# Power_Distribution_-_Spares_8-9_5V.net
KiCad netlist of a schematic drawn in Altium Designer
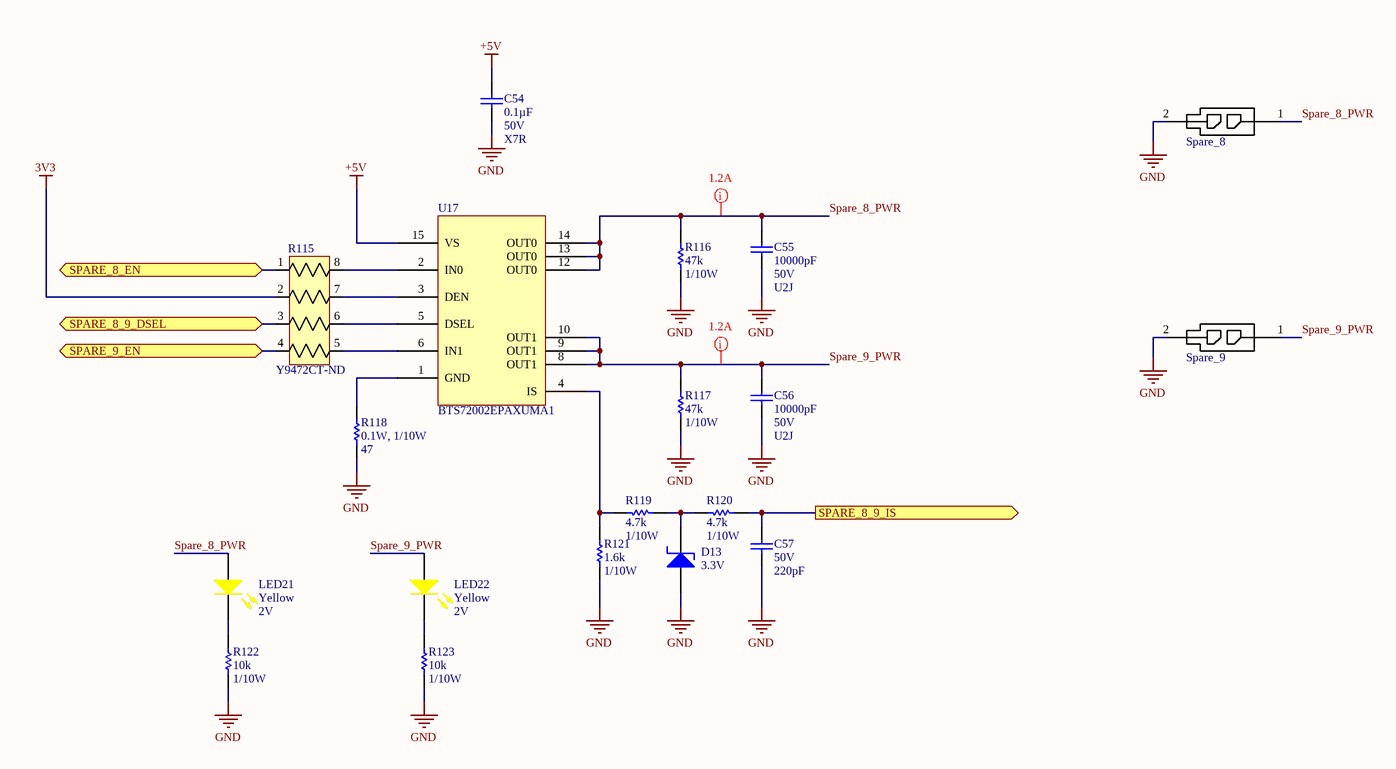
[diagram p0: Power Distribution - Spares 8-9 (5V).SchDoc]

(export (version "E")
  (design (tool "Eeschema 10.0.6"))
  (components
    (comp (ref "C54")
      (value "CAP CER 0.1UF 50V 10% X7R 0603")
      (footprint "CAP, 0603")
      (description "0.10µF ±10% 50V Ceramic Capacitor X7R 0603 (1608 Metric)")
      (fields
        (field (name "TOLERANCE") "±10%")
        (field (name "CAPACITANCE") "0.1µF")
        (field (name "VOLTAGE") "50V")
        (field (name "TEMPERATURE COEFFICIENT") "X7R")
      )
      (libsource (lib "Schematic Diagrams") (part "CAP CER 0.1UF 50V 10% X7R 0603"))
    )
    (comp (ref "C55")
      (value "CAP CER 10nF 50V 5% X7R 0603")
      (footprint "CAP, 0603")
      (description "10000pF ±5% 50V Ceramic Capacitor U2J 0603 (1608 Metric)")
      (fields
        (field (name "TOLERANCE") "±5%")
        (field (name "CAPACITANCE") "10000pF")
        (field (name "VOLTAGE") "50V")
        (field (name "TEMPERATURE COEFFICIENT") "U2J")
      )
      (libsource (lib "Schematic Diagrams") (part "CAP CER 10nF 50V 5% X7R 0603"))
    )
    (comp (ref "C56")
      (value "CAP CER 10nF 50V 5% X7R 0603")
      (footprint "CAP, 0603")
      (description "10000pF ±5% 50V Ceramic Capacitor U2J 0603 (1608 Metric)")
      (fields
        (field (name "TOLERANCE") "±5%")
        (field (name "CAPACITANCE") "10000pF")
        (field (name "VOLTAGE") "50V")
        (field (name "TEMPERATURE COEFFICIENT") "U2J")
      )
      (libsource (lib "Schematic Diagrams") (part "CAP CER 10nF 50V 5% X7R 0603"))
    )
    (comp (ref "C57")
      (value "CAP CER 220PF 50V C0G/NP0 0603")
      (footprint "CAP, 0603")
      (description "220pF ±5% 50V Ceramic Capacitor C0G, NP0 0603 (1608 Metric)")
      (fields
        (field (name "MANUFACTURER") "KEMET")
        (field (name "TOLERANCE") "5%")
        (field (name "VOLTAGE RATING") "50V")
        (field (name "CAPACITANCE") "220pF")
      )
      (libsource (lib "Schematic Diagrams") (part "CAP CER 220PF 50V C0G/NP0 0603"))
    )
    (comp (ref "D13")
      (value "DIODE ZENER 3.3V 200MW SOD323")
      (footprint "sod-323")
      (description "Zener Diode 3.3V 200mW ±5% Surface Mount SOD-323")
      (fields (field (name "VOLTAGE") "3.3V"))
      (libsource (lib "Schematic Diagrams") (part "DIODE ZENER 3.3V 200MW SOD323"))
    )
    (comp (ref "LED21")
      (value "LED YELLOW CLEAR 2.1V 0603")
      (footprint "LED_0603")
      (description "Yellow 590nm LED Indication - Discrete 2V 0603 (1608 Metric)")
      (fields
        (field (name "MANUFACTURER") "Wurth Electronics Inc.")
        (field (name "MANUFACTURER PART NUMBER") "150060YS75000")
        (field (name "COLOR") "Yellow")
        (field (name "VOLTAGE - FORWARD (VF) (TYP)") "2V")
      )
      (libsource (lib "Schematic Diagrams") (part "LED YELLOW CLEAR 2.1V 0603"))
    )
    (comp (ref "LED22")
      (value "LED YELLOW CLEAR 2.1V 0603")
      (footprint "LED_0603")
      (description "Yellow 590nm LED Indication - Discrete 2V 0603 (1608 Metric)")
      (fields
        (field (name "MANUFACTURER") "Wurth Electronics Inc.")
        (field (name "MANUFACTURER PART NUMBER") "150060YS75000")
        (field (name "COLOR") "Yellow")
        (field (name "VOLTAGE - FORWARD (VF) (TYP)") "2V")
      )
      (libsource (lib "Schematic Diagrams") (part "LED YELLOW CLEAR 2.1V 0603"))
    )
    (comp (ref "R115")
      (value "RES ARRAY 4 RES 4.7K OHM 1206")
      (footprint "RES ARRAY 4RES 1206")
      (fields (field (name "TOLERANCE") "±5%") (field (name "SUPPLIER PART NUMBER 1") "Y9472CT-ND"))
      (libsource (lib "Schematic Diagrams") (part "RES ARRAY 4 RES 4.7K OHM 1206"))
    )
    (comp (ref "R116")
      (value "RES 47K OHM 1% 1/10W 0603")
      (footprint "RES, 0603")
      (description "47 kOhms ±1% 0.1W, 1/10W Chip Resistor 0603 (1608 Metric) Automotive AEC-Q200 Thick Film")
      (fields
        (field (name "MANUFACTURER") "Panasonic")
        (field (name "MANUFACTURER PART NUMBER") "ERJ3EKF4702V")
        (field (name "RESISTANCE") "47k")
        (field (name "POWER RATING") "1/10W")
      )
      (libsource (lib "Schematic Diagrams") (part "RES 47K OHM 1% 1/10W 0603"))
    )
    (comp (ref "R117")
      (value "RES 47K OHM 1% 1/10W 0603")
      (footprint "RES, 0603")
      (description "47 kOhms ±1% 0.1W, 1/10W Chip Resistor 0603 (1608 Metric) Automotive AEC-Q200 Thick Film")
      (fields
        (field (name "MANUFACTURER") "Panasonic")
        (field (name "MANUFACTURER PART NUMBER") "ERJ3EKF4702V")
        (field (name "RESISTANCE") "47k")
        (field (name "POWER RATING") "1/10W")
      )
      (libsource (lib "Schematic Diagrams") (part "RES 47K OHM 1% 1/10W 0603"))
    )
    (comp (ref "R118")
      (value "RES SMD 47 OHM 1% 1/10W 0603")
      (footprint "RES, 0603")
      (fields
        (field (name "TOLERANCE") "±1%")
        (field (name "POWER (WATTS)") "0.1W, 1/10W")
        (field (name "VALUES") "47")
      )
      (libsource (lib "Schematic Diagrams") (part "RES SMD 47 OHM 1% 1/10W 0603"))
    )
    (comp (ref "R119")
      (value "RES 4.7K OHM 1% 1/10W 0603")
      (footprint "RES, 0603")
      (description "4.7k Ohm ±1% 0.1W, 1/10W Chip Resistor 0603 (1608 Metric) Moisture Resistant Thick Film")
      (fields
        (field (name "TOLERANCE") "±1%")
        (field (name "RESISTANCE (OHMS)") "4.7k")
        (field (name "POWER (WATTS)") "1/10W")
      )
      (libsource (lib "Schematic Diagrams") (part "RES 4.7K OHM 1% 1/10W 0603"))
    )
    (comp (ref "R120")
      (value "RES 4.7K OHM 1% 1/10W 0603")
      (footprint "RES, 0603")
      (description "4.7k Ohm ±1% 0.1W, 1/10W Chip Resistor 0603 (1608 Metric) Moisture Resistant Thick Film")
      (fields
        (field (name "TOLERANCE") "±1%")
        (field (name "RESISTANCE (OHMS)") "4.7k")
        (field (name "POWER (WATTS)") "1/10W")
      )
      (libsource (lib "Schematic Diagrams") (part "RES 4.7K OHM 1% 1/10W 0603"))
    )
    (comp (ref "R121")
      (value "RES 1.6K OHM 1% 1/10W 0603")
      (footprint "RES, 0603")
      (description "1.6 kOhms ±1% 0.1W, 1/10W Chip Resistor 0603 (1608 Metric) Moisture Resistant Thick Film")
      (fields
        (field (name "MANUFACTURER") "Yageo")
        (field (name "MANUFACTURER PART NUMBER") "RC0603FR-071K6L")
        (field (name "RESISTANCE") "1.6k")
        (field (name "POWER RATING") "1/10W")
      )
      (libsource (lib "Schematic Diagrams") (part "RES 1.6K OHM 1% 1/10W 0603"))
    )
    (comp (ref "R122")
      (value "RES 10K OHM 1% 1/10W 0603")
      (footprint "RES, 0603")
      (description "RES SMD 10K OHM 1% 1/10W 0603")
      (fields
        (field (name "TOLERANCE") "±1%")
        (field (name "RESISTANCE") "10k")
        (field (name "POWER") "1/10W")
      )
      (libsource (lib "Schematic Diagrams") (part "RES 10K OHM 1% 1/10W 0603"))
    )
    (comp (ref "R123")
      (value "RES 10K OHM 1% 1/10W 0603")
      (footprint "RES, 0603")
      (description "RES SMD 10K OHM 1% 1/10W 0603")
      (fields
        (field (name "TOLERANCE") "±1%")
        (field (name "RESISTANCE") "10k")
        (field (name "POWER") "1/10W")
      )
      (libsource (lib "Schematic Diagrams") (part "RES 10K OHM 1% 1/10W 0603"))
    )
    (comp (ref "Spare_8")
      (value "CONN 2POS MICRO-FIT 3mm")
      (footprint "CONN, 2POS MICRO-FIT")
      (description "Connector Header Through Hole 2 position")
      (fields (field (name "MANUFACTURER") "Molex") (field (name "MANUFACTURER PART NUMBER") "43045-0227"))
      (libsource (lib "Schematic Diagrams") (part "CONN 2POS MICRO-FIT 3mm"))
    )
    (comp (ref "Spare_9")
      (value "CONN 2POS MICRO-FIT 3mm")
      (footprint "CONN, 2POS MICRO-FIT")
      (description "Connector Header Through Hole 2 position")
      (fields (field (name "MANUFACTURER") "Molex") (field (name "MANUFACTURER PART NUMBER") "43045-0227"))
      (libsource (lib "Schematic Diagrams") (part "CONN 2POS MICRO-FIT 3mm"))
    )
    (comp (ref "U17")
      (value "IC LOAD SWITCH BTS7200-2EPA PG-TSDSO-14_1")
      (footprint "IC LOAD SWITCH PG-TSDSO-14-22")
      (description "Power Switch/Driver 1:1 N-Channel 1.2A PG-TSDSO-14-22")
      (fields
        (field (name "MANUFACTURER") "Infineon")
        (field (name "MANUFACTURER PART NUMBER") "BTS72002EPAXUMA1")
      )
      (libsource (lib "Schematic Diagrams") (part "IC LOAD SWITCH BTS7200-2EPA PG-TSDSO-14_1"))
    )
  )
  (nets
    (net (code "1") (name "+5V") (class "Default")
      (node (ref "C54") (pin "1") (pinfunction "1_1") (pintype "passive"))
      (node (ref "U17") (pin "15") (pinfunction "VS_15") (pintype "passive"))
    )
    (net (code "2") (name "/SPARE_8_9_DSEL") (class "Default")
      (node (ref "R115") (pin "3") (pinfunction "3_3") (pintype "passive"))
    )
    (net (code "3") (name "/SPARE_8_9_IS") (class "Default")
      (node (ref "C57") (pin "1") (pinfunction "1_1") (pintype "passive"))
      (node (ref "R120") (pin "1") (pinfunction "1_1") (pintype "passive"))
    )
    (net (code "4") (name "/SPARE_8_EN") (class "Default")
      (node (ref "R115") (pin "1") (pinfunction "1_1") (pintype "passive"))
    )
    (net (code "5") (name "/SPARE_9_EN") (class "Default")
      (node (ref "R115") (pin "4") (pinfunction "4_4") (pintype "passive"))
    )
    (net (code "6") (name "/Spare_8_PWR") (class "Default")
      (node (ref "C55") (pin "1") (pinfunction "1_1") (pintype "passive"))
      (node (ref "LED21") (pin "1") (pinfunction "A_1") (pintype "passive"))
      (node (ref "R116") (pin "1") (pinfunction "1_1") (pintype "passive"))
      (node (ref "Spare_8") (pin "1") (pinfunction "1_1") (pintype "passive"))
      (node (ref "U17") (pin "12") (pinfunction "OUT0_12") (pintype "passive"))
      (node (ref "U17") (pin "13") (pinfunction "OUT0_13") (pintype "passive"))
      (node (ref "U17") (pin "14") (pinfunction "OUT0_14") (pintype "passive"))
    )
    (net (code "7") (name "/Spare_9_PWR") (class "Default")
      (node (ref "C56") (pin "1") (pinfunction "1_1") (pintype "passive"))
      (node (ref "LED22") (pin "1") (pinfunction "A_1") (pintype "passive"))
      (node (ref "R117") (pin "1") (pinfunction "1_1") (pintype "passive"))
      (node (ref "Spare_9") (pin "1") (pinfunction "1_1") (pintype "passive"))
      (node (ref "U17") (pin "10") (pinfunction "OUT1_10") (pintype "passive"))
      (node (ref "U17") (pin "8") (pinfunction "OUT1_8") (pintype "passive"))
      (node (ref "U17") (pin "9") (pinfunction "OUT1_9") (pintype "passive"))
    )
    (net (code "8") (name "3V3") (class "Default")
      (node (ref "R115") (pin "2") (pinfunction "2_2") (pintype "passive"))
    )
    (net (code "9") (name "GND") (class "Default")
      (node (ref "C54") (pin "2") (pinfunction "2_2") (pintype "passive"))
      (node (ref "C55") (pin "2") (pinfunction "2_2") (pintype "passive"))
      (node (ref "C56") (pin "2") (pinfunction "2_2") (pintype "passive"))
      (node (ref "C57") (pin "2") (pinfunction "2_2") (pintype "passive"))
      (node (ref "D13") (pin "1") (pinfunction "A_1") (pintype "passive"))
      (node (ref "R116") (pin "2") (pinfunction "2_2") (pintype "passive"))
      (node (ref "R117") (pin "2") (pinfunction "2_2") (pintype "passive"))
      (node (ref "R118") (pin "2") (pinfunction "2_2") (pintype "passive"))
      (node (ref "R121") (pin "2") (pinfunction "2_2") (pintype "passive"))
      (node (ref "R122") (pin "2") (pinfunction "2_2") (pintype "passive"))
      (node (ref "R123") (pin "2") (pinfunction "2_2") (pintype "passive"))
      (node (ref "Spare_8") (pin "2") (pinfunction "2_2") (pintype "passive"))
      (node (ref "Spare_9") (pin "2") (pinfunction "2_2") (pintype "passive"))
    )
    (net (code "10") (name "Net-(D13-K)") (class "Default")
      (node (ref "D13") (pin "2") (pinfunction "K_2") (pintype "passive"))
      (node (ref "R119") (pin "1") (pinfunction "1_1") (pintype "passive"))
      (node (ref "R120") (pin "2") (pinfunction "2_2") (pintype "passive"))
    )
    (net (code "11") (name "Net-(LED21-K)") (class "Default")
      (node (ref "LED21") (pin "2") (pinfunction "K_2") (pintype "passive"))
      (node (ref "R122") (pin "1") (pinfunction "1_1") (pintype "passive"))
    )
    (net (code "12") (name "Net-(LED22-K)") (class "Default")
      (node (ref "LED22") (pin "2") (pinfunction "K_2") (pintype "passive"))
      (node (ref "R123") (pin "1") (pinfunction "1_1") (pintype "passive"))
    )
    (net (code "13") (name "Net-(U17-DEN)") (class "Default")
      (node (ref "R115") (pin "7") (pinfunction "7_7") (pintype "passive"))
      (node (ref "U17") (pin "3") (pinfunction "DEN_3") (pintype "passive"))
    )
    (net (code "14") (name "Net-(U17-DSEL)") (class "Default")
      (node (ref "R115") (pin "6") (pinfunction "6_6") (pintype "passive"))
      (node (ref "U17") (pin "5") (pinfunction "DSEL_5") (pintype "passive"))
    )
    (net (code "15") (name "Net-(U17-GND)") (class "Default")
      (node (ref "R118") (pin "1") (pinfunction "1_1") (pintype "passive"))
      (node (ref "U17") (pin "1") (pinfunction "GND_1") (pintype "passive"))
    )
    (net (code "16") (name "Net-(U17-IN0)") (class "Default")
      (node (ref "R115") (pin "8") (pinfunction "8_8") (pintype "passive"))
      (node (ref "U17") (pin "2") (pinfunction "IN0_2") (pintype "passive"))
    )
    (net (code "17") (name "Net-(U17-IN1)") (class "Default")
      (node (ref "R115") (pin "5") (pinfunction "5_5") (pintype "passive"))
      (node (ref "U17") (pin "6") (pinfunction "IN1_6") (pintype "passive"))
    )
    (net (code "18") (name "Net-(U17-IS)") (class "Default")
      (node (ref "R119") (pin "2") (pinfunction "2_2") (pintype "passive"))
      (node (ref "R121") (pin "1") (pinfunction "1_1") (pintype "passive"))
      (node (ref "U17") (pin "4") (pinfunction "IS_4") (pintype "passive"))
    )
  )
)
